# ESP-WROOM-32D.net
KiCad netlist of a schematic drawn in Altium Designer
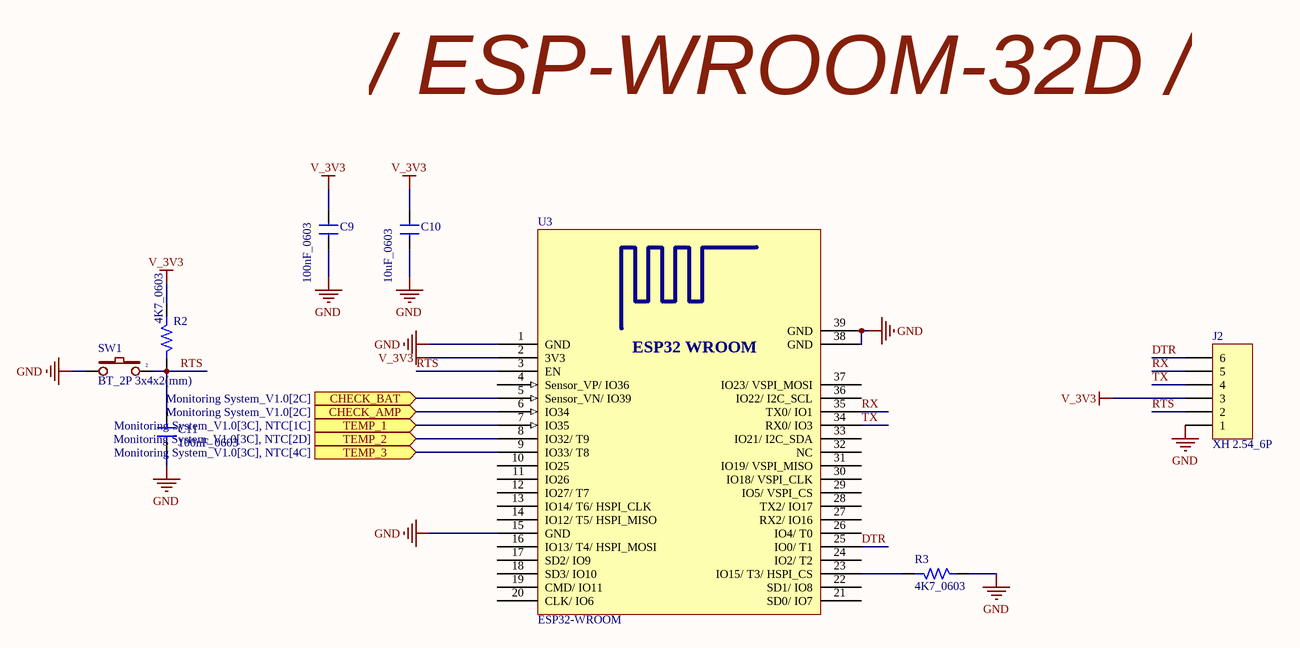
[diagram p0: ESP-WROOM-32D.SchDoc]

(export (version "E")
  (design (tool "Eeschema 10.0.6"))
  (components
    (comp (ref "C9")
      (value "100nF_0603")
      (footprint "CN-SMD-0603")
      (description "Cap SMD, 0.06x0.03 inch, 1.55x0.85 mm - 1608")
      (libsource (lib "LYAM_LIB") (part "CAP 0603 104"))
    )
    (comp (ref "C10")
      (value "10uF_0603")
      (footprint "CN-SMD-0603")
      (description "Cap SMD, 0.06x0.03 inch, 1.55x0.85 mm - 1608")
      (libsource (lib "LYAM_LIB") (part "CAP 0603 106"))
    )
    (comp (ref "C11")
      (value "100nF_0603")
      (footprint "CN-SMD-0603")
      (description "Cap SMD, 0.06x0.03 inch, 1.55x0.85 mm - 1608")
      (libsource (lib "LYAM_LIB") (part "CAP 0603 104"))
    )
    (comp (ref "J2")
      (value "XH 2.54_6P")
      (footprint "JP6_Boot")
      (libsource (lib "LYAM_LIB") (part "XH 2.54_6P_Boot"))
    )
    (comp (ref "R2")
      (value "4K7_0603")
      (footprint "RES-SMD-0603")
      (description "Resistor SMD, 0.06x0.03 inch, 1.55x0.85 mm - 1608, 1/10W")
      (libsource (lib "LYAM_LIB") (part "RES 0603 4K7"))
    )
    (comp (ref "R3")
      (value "4K7_0603")
      (footprint "RES-SMD-0603")
      (description "Resistor SMD, 0.06x0.03 inch, 1.55x0.85 mm - 1608, 1/10W")
      (libsource (lib "LYAM_LIB") (part "RES 0603 4K7"))
    )
    (comp (ref "SW1")
      (value "BT_2P 3x4x2(mm)")
      (footprint "BUTTON 2P 3X4X2MM")
      (description "Switch button 2 pin")
      (libsource (lib "LYAM_LIB") (part "BT_2P 3x4x2(mm)"))
    )
    (comp (ref "U3")
      (value "ESP32-WROOM")
      (footprint "ESP32 WROOM")
      (description "ESP32 WROOM, 3.0 V ~ 3.6 V, 80mA.")
      (libsource (lib "LYAM_LIB") (part "ESP32-WROOM"))
    )
  )
  (nets
    (net (code "1") (name "/CHECK_AMP") (class "Default")
      (node (ref "U3") (pin "6") (pinfunction "IO34_6") (pintype "input"))
    )
    (net (code "2") (name "/CHECK_BAT") (class "Default")
      (node (ref "U3") (pin "5") (pinfunction "Sensor_VN/_IO39_5") (pintype "input"))
    )
    (net (code "3") (name "/DTR") (class "Default")
      (node (ref "J2") (pin "6") (pinfunction "6_6") (pintype "passive"))
      (node (ref "U3") (pin "25") (pinfunction "IO0/_T1_25") (pintype "passive"))
    )
    (net (code "4") (name "/RTS") (class "Default")
      (node (ref "C11") (pin "1") (pinfunction "1_1") (pintype "passive"))
      (node (ref "J2") (pin "2") (pinfunction "2_2") (pintype "passive"))
      (node (ref "R2") (pin "1") (pinfunction "1_1") (pintype "passive"))
      (node (ref "SW1") (pin "2") (pinfunction "2_2") (pintype "passive"))
      (node (ref "U3") (pin "3") (pinfunction "EN_3") (pintype "passive"))
    )
    (net (code "5") (name "/RX") (class "Default")
      (node (ref "J2") (pin "5") (pinfunction "5_5") (pintype "passive"))
      (node (ref "U3") (pin "35") (pinfunction "TX0/_IO1_35") (pintype "passive"))
    )
    (net (code "6") (name "/TEMP_1") (class "Default")
      (node (ref "U3") (pin "7") (pinfunction "IO35_7") (pintype "input"))
    )
    (net (code "7") (name "/TEMP_2") (class "Default")
      (node (ref "U3") (pin "8") (pinfunction "IO32/_T9_8") (pintype "passive"))
    )
    (net (code "8") (name "/TEMP_3") (class "Default")
      (node (ref "U3") (pin "9") (pinfunction "IO33/_T8_9") (pintype "passive"))
    )
    (net (code "9") (name "/TX") (class "Default")
      (node (ref "J2") (pin "4") (pinfunction "4_4") (pintype "passive"))
      (node (ref "U3") (pin "34") (pinfunction "RX0/_IO3_34") (pintype "passive"))
    )
    (net (code "10") (name "GND") (class "Default")
      (node (ref "C10") (pin "1") (pinfunction "1_1") (pintype "passive"))
      (node (ref "C11") (pin "2") (pinfunction "2_2") (pintype "passive"))
      (node (ref "C9") (pin "1") (pinfunction "1_1") (pintype "passive"))
      (node (ref "J2") (pin "1") (pinfunction "1_1") (pintype "passive"))
      (node (ref "R3") (pin "1") (pinfunction "1_1") (pintype "passive"))
      (node (ref "SW1") (pin "1") (pinfunction "1_1") (pintype "passive"))
      (node (ref "U3") (pin "1") (pinfunction "GND_1") (pintype "passive"))
      (node (ref "U3") (pin "15") (pinfunction "GND_15") (pintype "passive"))
      (node (ref "U3") (pin "38") (pinfunction "GND_38") (pintype "passive"))
      (node (ref "U3") (pin "39") (pinfunction "GND_39") (pintype "passive"))
    )
    (net (code "11") (name "Net-(U3-IO15{slash}_T3{slash}_HSPI_CS)") (class "Default")
      (node (ref "R3") (pin "2") (pinfunction "2_2") (pintype "passive"))
      (node (ref "U3") (pin "23") (pinfunction "IO15/_T3/_HSPI_CS_23") (pintype "passive"))
    )
    (net (code "12") (name "V_3V3") (class "Default")
      (node (ref "C10") (pin "2") (pinfunction "2_2") (pintype "passive"))
      (node (ref "C9") (pin "2") (pinfunction "2_2") (pintype "passive"))
      (node (ref "J2") (pin "3") (pinfunction "3_3") (pintype "passive"))
      (node (ref "R2") (pin "2") (pinfunction "2_2") (pintype "passive"))
      (node (ref "U3") (pin "2") (pinfunction "3V3_2") (pintype "passive"))
    )
    (net (code "13") (name "unconnected-(U3-CLK{slash}_IO6-Pad20)") (class "Default")
      (node (ref "U3") (pin "20") (pinfunction "CLK/_IO6_20") (pintype "passive"))
    )
    (net (code "14") (name "unconnected-(U3-CMD{slash}_IO11-Pad19)") (class "Default")
      (node (ref "U3") (pin "19") (pinfunction "CMD/_IO11_19") (pintype "passive"))
    )
    (net (code "15") (name "unconnected-(U3-IO2{slash}_T2-Pad24)") (class "Default")
      (node (ref "U3") (pin "24") (pinfunction "IO2/_T2_24") (pintype "passive"))
    )
    (net (code "16") (name "unconnected-(U3-IO4{slash}_T0-Pad26)") (class "Default")
      (node (ref "U3") (pin "26") (pinfunction "IO4/_T0_26") (pintype "passive"))
    )
    (net (code "17") (name "unconnected-(U3-IO5{slash}_VSPI_CS-Pad29)") (class "Default")
      (node (ref "U3") (pin "29") (pinfunction "IO5/_VSPI_CS_29") (pintype "passive"))
    )
    (net (code "18") (name "unconnected-(U3-IO12{slash}_T5{slash}_HSPI_MISO-Pad14)") (class "Default")
      (node (ref "U3") (pin "14") (pinfunction "IO12/_T5/_HSPI_MISO_14") (pintype "passive"))
    )
    (net (code "19") (name "unconnected-(U3-IO13{slash}_T4{slash}_HSPI_MOSI-Pad16)") (class "Default")
      (node (ref "U3") (pin "16") (pinfunction "IO13/_T4/_HSPI_MOSI_16") (pintype "passive"))
    )
    (net (code "20") (name "unconnected-(U3-IO14{slash}_T6{slash}_HSPI_CLK-Pad13)") (class "Default")
      (node (ref "U3") (pin "13") (pinfunction "IO14/_T6/_HSPI_CLK_13") (pintype "passive"))
    )
    (net (code "21") (name "unconnected-(U3-IO18{slash}_VSPI_CLK-Pad30)") (class "Default")
      (node (ref "U3") (pin "30") (pinfunction "IO18/_VSPI_CLK_30") (pintype "passive"))
    )
    (net (code "22") (name "unconnected-(U3-IO19{slash}_VSPI_MISO-Pad31)") (class "Default")
      (node (ref "U3") (pin "31") (pinfunction "IO19/_VSPI_MISO_31") (pintype "passive"))
    )
    (net (code "23") (name "unconnected-(U3-IO21{slash}_I2C_SDA-Pad33)") (class "Default")
      (node (ref "U3") (pin "33") (pinfunction "IO21/_I2C_SDA_33") (pintype "passive"))
    )
    (net (code "24") (name "unconnected-(U3-IO22{slash}_I2C_SCL-Pad36)") (class "Default")
      (node (ref "U3") (pin "36") (pinfunction "IO22/_I2C_SCL_36") (pintype "passive"))
    )
    (net (code "25") (name "unconnected-(U3-IO23{slash}_VSPI_MOSI-Pad37)") (class "Default")
      (node (ref "U3") (pin "37") (pinfunction "IO23/_VSPI_MOSI_37") (pintype "passive"))
    )
    (net (code "26") (name "unconnected-(U3-IO25-Pad10)") (class "Default")
      (node (ref "U3") (pin "10") (pinfunction "IO25_10") (pintype "passive"))
    )
    (net (code "27") (name "unconnected-(U3-IO26-Pad11)") (class "Default")
      (node (ref "U3") (pin "11") (pinfunction "IO26_11") (pintype "passive"))
    )
    (net (code "28") (name "unconnected-(U3-IO27{slash}_T7-Pad12)") (class "Default")
      (node (ref "U3") (pin "12") (pinfunction "IO27/_T7_12") (pintype "passive"))
    )
    (net (code "29") (name "unconnected-(U3-NC-Pad32)") (class "Default")
      (node (ref "U3") (pin "32") (pinfunction "NC_32") (pintype "passive"))
    )
    (net (code "30") (name "unconnected-(U3-RX2{slash}_IO16-Pad27)") (class "Default")
      (node (ref "U3") (pin "27") (pinfunction "RX2/_IO16_27") (pintype "passive"))
    )
    (net (code "31") (name "unconnected-(U3-SD0{slash}_IO7-Pad21)") (class "Default")
      (node (ref "U3") (pin "21") (pinfunction "SD0/_IO7_21") (pintype "passive"))
    )
    (net (code "32") (name "unconnected-(U3-SD1{slash}_IO8-Pad22)") (class "Default")
      (node (ref "U3") (pin "22") (pinfunction "SD1/_IO8_22") (pintype "passive"))
    )
    (net (code "33") (name "unconnected-(U3-SD2{slash}_IO9-Pad17)") (class "Default")
      (node (ref "U3") (pin "17") (pinfunction "SD2/_IO9_17") (pintype "passive"))
    )
    (net (code "34") (name "unconnected-(U3-SD3{slash}_IO10-Pad18)") (class "Default")
      (node (ref "U3") (pin "18") (pinfunction "SD3/_IO10_18") (pintype "passive"))
    )
    (net (code "35") (name "unconnected-(U3-Sensor_VP{slash}_IO36-Pad4)") (class "Default")
      (node (ref "U3") (pin "4") (pinfunction "Sensor_VP/_IO36_4") (pintype "input"))
    )
    (net (code "36") (name "unconnected-(U3-TX2{slash}_IO17-Pad28)") (class "Default")
      (node (ref "U3") (pin "28") (pinfunction "TX2/_IO17_28") (pintype "passive"))
    )
  )
)
